# s-tuner_bread_board.net
KiCad netlist of a schematic drawn in EAGLE
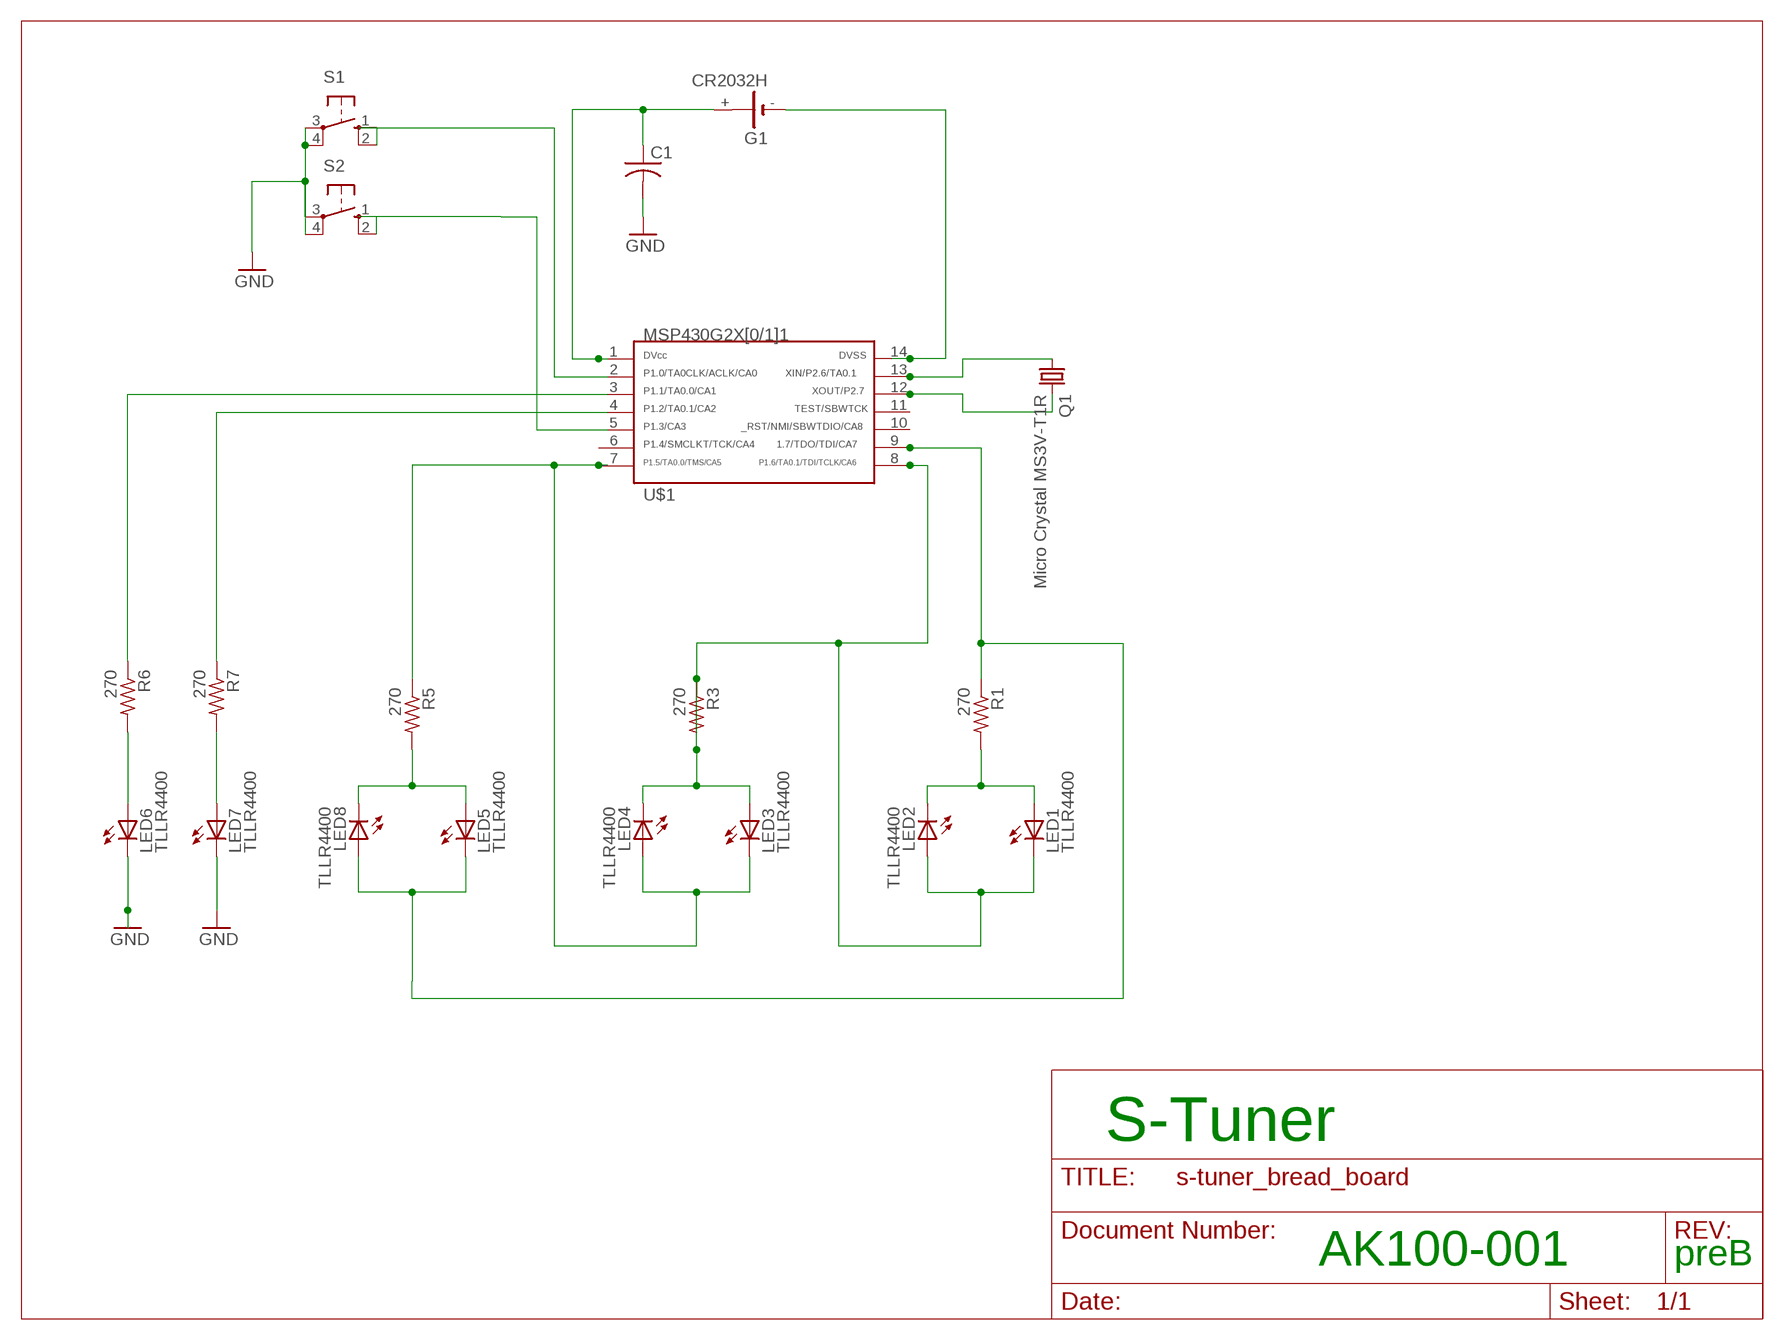
[diagram p0: schematic, sheet 1]

(export (version "E")
  (design (tool "Eeschema 10.0.6"))
  (components
    (comp (ref "C1")
      (value "C-US025-024X044")
      (footprint "eagle-import:C025-024X044")
      (libsource (lib "eagle-import") (part "C-US025-024X044"))
    )
    (comp (ref "G1")
      (value "CR2032H")
      (footprint "eagle-import:CR2032H")
      (libsource (lib "eagle-import") (part "CR2032H"))
    )
    (comp (ref "LED1")
      (value "TLLR4400")
      (footprint "eagle-import:LED3MM")
      (fields (field (name "MF") "VISHAY SEMICONDUCTOR"))
      (libsource (lib "eagle-import") (part "TLLR4400"))
    )
    (comp (ref "LED2")
      (value "TLLR4400")
      (footprint "eagle-import:LED3MM")
      (fields (field (name "MF") "VISHAY SEMICONDUCTOR"))
      (libsource (lib "eagle-import") (part "TLLR4400"))
    )
    (comp (ref "LED3")
      (value "TLLR4400")
      (footprint "eagle-import:LED3MM")
      (fields (field (name "MF") "VISHAY SEMICONDUCTOR"))
      (libsource (lib "eagle-import") (part "TLLR4400"))
    )
    (comp (ref "LED4")
      (value "TLLR4400")
      (footprint "eagle-import:LED3MM")
      (fields (field (name "MF") "VISHAY SEMICONDUCTOR"))
      (libsource (lib "eagle-import") (part "TLLR4400"))
    )
    (comp (ref "LED5")
      (value "TLLR4400")
      (footprint "eagle-import:LED3MM")
      (fields (field (name "MF") "VISHAY SEMICONDUCTOR"))
      (libsource (lib "eagle-import") (part "TLLR4400"))
    )
    (comp (ref "LED6")
      (value "TLLR4400")
      (footprint "eagle-import:LED3MM")
      (fields (field (name "MF") "VISHAY SEMICONDUCTOR"))
      (libsource (lib "eagle-import") (part "TLLR4400"))
    )
    (comp (ref "LED7")
      (value "TLLR4400")
      (footprint "eagle-import:LED3MM")
      (fields (field (name "MF") "VISHAY SEMICONDUCTOR"))
      (libsource (lib "eagle-import") (part "TLLR4400"))
    )
    (comp (ref "LED8")
      (value "TLLR4400")
      (footprint "eagle-import:LED3MM")
      (fields (field (name "MF") "VISHAY SEMICONDUCTOR"))
      (libsource (lib "eagle-import") (part "TLLR4400"))
    )
    (comp (ref "Q1")
      (value "Micro Crystal MS3V-T1R")
      (footprint "eagle-import:TC26H")
      (libsource (lib "eagle-import") (part "CRYSTALTC26H"))
    )
    (comp (ref "R1")
      (value "270")
      (footprint "eagle-import:R0603")
      (libsource (lib "eagle-import") (part "R-US_R0603"))
    )
    (comp (ref "R3")
      (value "270")
      (footprint "eagle-import:R0603")
      (libsource (lib "eagle-import") (part "R-US_R0603"))
    )
    (comp (ref "R5")
      (value "270")
      (footprint "eagle-import:R0603")
      (libsource (lib "eagle-import") (part "R-US_R0603"))
    )
    (comp (ref "R6")
      (value "270")
      (footprint "eagle-import:R0603")
      (libsource (lib "eagle-import") (part "R-US_R0603"))
    )
    (comp (ref "R7")
      (value "270")
      (footprint "eagle-import:R0603")
      (libsource (lib "eagle-import") (part "R-US_R0603"))
    )
    (comp (ref "S1")
      (value "10-XX")
      (footprint "eagle-import:B3F-10XX")
      (fields (field (name "MPN") "B3F-1000"))
      (libsource (lib "eagle-import") (part "10-XX"))
    )
    (comp (ref "S2")
      (value "10-XX")
      (footprint "eagle-import:B3F-10XX")
      (fields (field (name "MPN") "B3F-1000"))
      (libsource (lib "eagle-import") (part "10-XX"))
    )
    (comp (ref "U$1")
      (value "G2X[0/1]1---N14")
      (footprint "eagle-import:N14")
      (libsource (lib "eagle-import") (part "G2X[0/1]1---N14"))
    )
  )
  (nets
    (net (code "1") (name "GND") (class "Default")
      (node (ref "C1") (pin "2") (pinfunction "2_2") (pintype "passive"))
      (node (ref "LED6") (pin "K") (pinfunction "C_K") (pintype "passive"))
      (node (ref "LED7") (pin "K") (pinfunction "C_K") (pintype "passive"))
      (node (ref "S1") (pin "3") (pinfunction "P_3") (pintype "passive"))
      (node (ref "S1") (pin "4") (pinfunction "P1_4") (pintype "passive"))
      (node (ref "S2") (pin "3") (pinfunction "P_3") (pintype "passive"))
      (node (ref "S2") (pin "4") (pinfunction "P1_4") (pintype "passive"))
    )
    (net (code "2") (name "Net-(C1-Pad1)") (class "Default")
      (node (ref "C1") (pin "1") (pinfunction "1_1") (pintype "passive"))
      (node (ref "G1") (pin "+") (pinfunction "+_+") (pintype "passive"))
      (node (ref "U$1") (pin "1") (pinfunction "1_1") (pintype "bidirectional"))
    )
    (net (code "3") (name "Net-(G1-Pad-)") (class "Default")
      (node (ref "G1") (pin "-") (pinfunction "-_-") (pintype "passive"))
      (node (ref "U$1") (pin "14") (pinfunction "14_14") (pintype "bidirectional"))
    )
    (net (code "4") (name "Net-(LED1-C)") (class "Default")
      (node (ref "LED1") (pin "K") (pinfunction "C_K") (pintype "passive"))
      (node (ref "LED2") (pin "A") (pinfunction "A_A") (pintype "passive"))
      (node (ref "LED3") (pin "A") (pinfunction "A_A") (pintype "passive"))
      (node (ref "LED4") (pin "K") (pinfunction "C_K") (pintype "passive"))
      (node (ref "R3") (pin "1") (pinfunction "1_1") (pintype "passive"))
      (node (ref "R3") (pin "2") (pinfunction "2_2") (pintype "passive"))
      (node (ref "U$1") (pin "8") (pinfunction "8_8") (pintype "bidirectional"))
    )
    (net (code "5") (name "Net-(LED2-C)") (class "Default")
      (node (ref "LED1") (pin "A") (pinfunction "A_A") (pintype "passive"))
      (node (ref "LED2") (pin "K") (pinfunction "C_K") (pintype "passive"))
      (node (ref "R1") (pin "2") (pinfunction "2_2") (pintype "passive"))
    )
    (net (code "6") (name "Net-(LED3-C)") (class "Default")
      (node (ref "LED3") (pin "K") (pinfunction "C_K") (pintype "passive"))
      (node (ref "LED4") (pin "A") (pinfunction "A_A") (pintype "passive"))
      (node (ref "R5") (pin "1") (pinfunction "1_1") (pintype "passive"))
      (node (ref "U$1") (pin "7") (pinfunction "7_7") (pintype "bidirectional"))
    )
    (net (code "7") (name "Net-(LED5-C)") (class "Default")
      (node (ref "LED5") (pin "K") (pinfunction "C_K") (pintype "passive"))
      (node (ref "LED8") (pin "A") (pinfunction "A_A") (pintype "passive"))
      (node (ref "R1") (pin "1") (pinfunction "1_1") (pintype "passive"))
      (node (ref "U$1") (pin "9") (pinfunction "9_9") (pintype "bidirectional"))
    )
    (net (code "8") (name "Net-(LED6-PadA)") (class "Default")
      (node (ref "LED6") (pin "A") (pinfunction "A_A") (pintype "passive"))
      (node (ref "R6") (pin "2") (pinfunction "2_2") (pintype "passive"))
    )
    (net (code "9") (name "Net-(LED7-PadA)") (class "Default")
      (node (ref "LED7") (pin "A") (pinfunction "A_A") (pintype "passive"))
      (node (ref "R7") (pin "2") (pinfunction "2_2") (pintype "passive"))
    )
    (net (code "10") (name "Net-(LED8-C)") (class "Default")
      (node (ref "LED5") (pin "A") (pinfunction "A_A") (pintype "passive"))
      (node (ref "LED8") (pin "K") (pinfunction "C_K") (pintype "passive"))
      (node (ref "R5") (pin "2") (pinfunction "2_2") (pintype "passive"))
    )
    (net (code "11") (name "Net-(Q1-Pad1)") (class "Default")
      (node (ref "Q1") (pin "1") (pinfunction "1_1") (pintype "passive"))
      (node (ref "U$1") (pin "13") (pinfunction "13_13") (pintype "bidirectional"))
    )
    (net (code "12") (name "Net-(Q1-Pad2)") (class "Default")
      (node (ref "Q1") (pin "2") (pinfunction "2_2") (pintype "passive"))
      (node (ref "U$1") (pin "12") (pinfunction "12_12") (pintype "bidirectional"))
    )
    (net (code "13") (name "Net-(S1-S)") (class "Default")
      (node (ref "S1") (pin "1") (pinfunction "S_1") (pintype "passive"))
      (node (ref "S1") (pin "2") (pinfunction "S1_2") (pintype "passive"))
    )
    (net (code "14") (name "Net-(S2-S)") (class "Default")
      (node (ref "S2") (pin "1") (pinfunction "S_1") (pintype "passive"))
      (node (ref "S2") (pin "2") (pinfunction "S1_2") (pintype "passive"))
    )
    (net (code "15") (name "unconnected-(G1-+-Pad+@1)") (class "Default")
      (node (ref "G1") (pin "+@1") (pinfunction "+_+@1") (pintype "passive"))
    )
    (net (code "16") (name "unconnected-(R6-Pad1)") (class "Default")
      (node (ref "R6") (pin "1") (pinfunction "1_1") (pintype "passive"))
    )
    (net (code "17") (name "unconnected-(R7-Pad1)") (class "Default")
      (node (ref "R7") (pin "1") (pinfunction "1_1") (pintype "passive"))
    )
    (net (code "18") (name "unconnected-(U$1-Pad2)") (class "Default")
      (node (ref "U$1") (pin "2") (pinfunction "2_2") (pintype "bidirectional"))
    )
    (net (code "19") (name "unconnected-(U$1-Pad3)") (class "Default")
      (node (ref "U$1") (pin "3") (pinfunction "3_3") (pintype "bidirectional"))
    )
    (net (code "20") (name "unconnected-(U$1-Pad4)") (class "Default")
      (node (ref "U$1") (pin "4") (pinfunction "4_4") (pintype "bidirectional"))
    )
    (net (code "21") (name "unconnected-(U$1-Pad5)") (class "Default")
      (node (ref "U$1") (pin "5") (pinfunction "5_5") (pintype "bidirectional"))
    )
    (net (code "22") (name "unconnected-(U$1-Pad6)") (class "Default")
      (node (ref "U$1") (pin "6") (pinfunction "6_6") (pintype "bidirectional"))
    )
    (net (code "23") (name "unconnected-(U$1-Pad10)") (class "Default")
      (node (ref "U$1") (pin "10") (pinfunction "10_10") (pintype "bidirectional"))
    )
    (net (code "24") (name "unconnected-(U$1-Pad11)") (class "Default")
      (node (ref "U$1") (pin "11") (pinfunction "11_11") (pintype "bidirectional"))
    )
  )
)
